# ultra-violet-tooth-sensor-mk-2_2.net
KiCad netlist of a schematic drawn in EAGLE
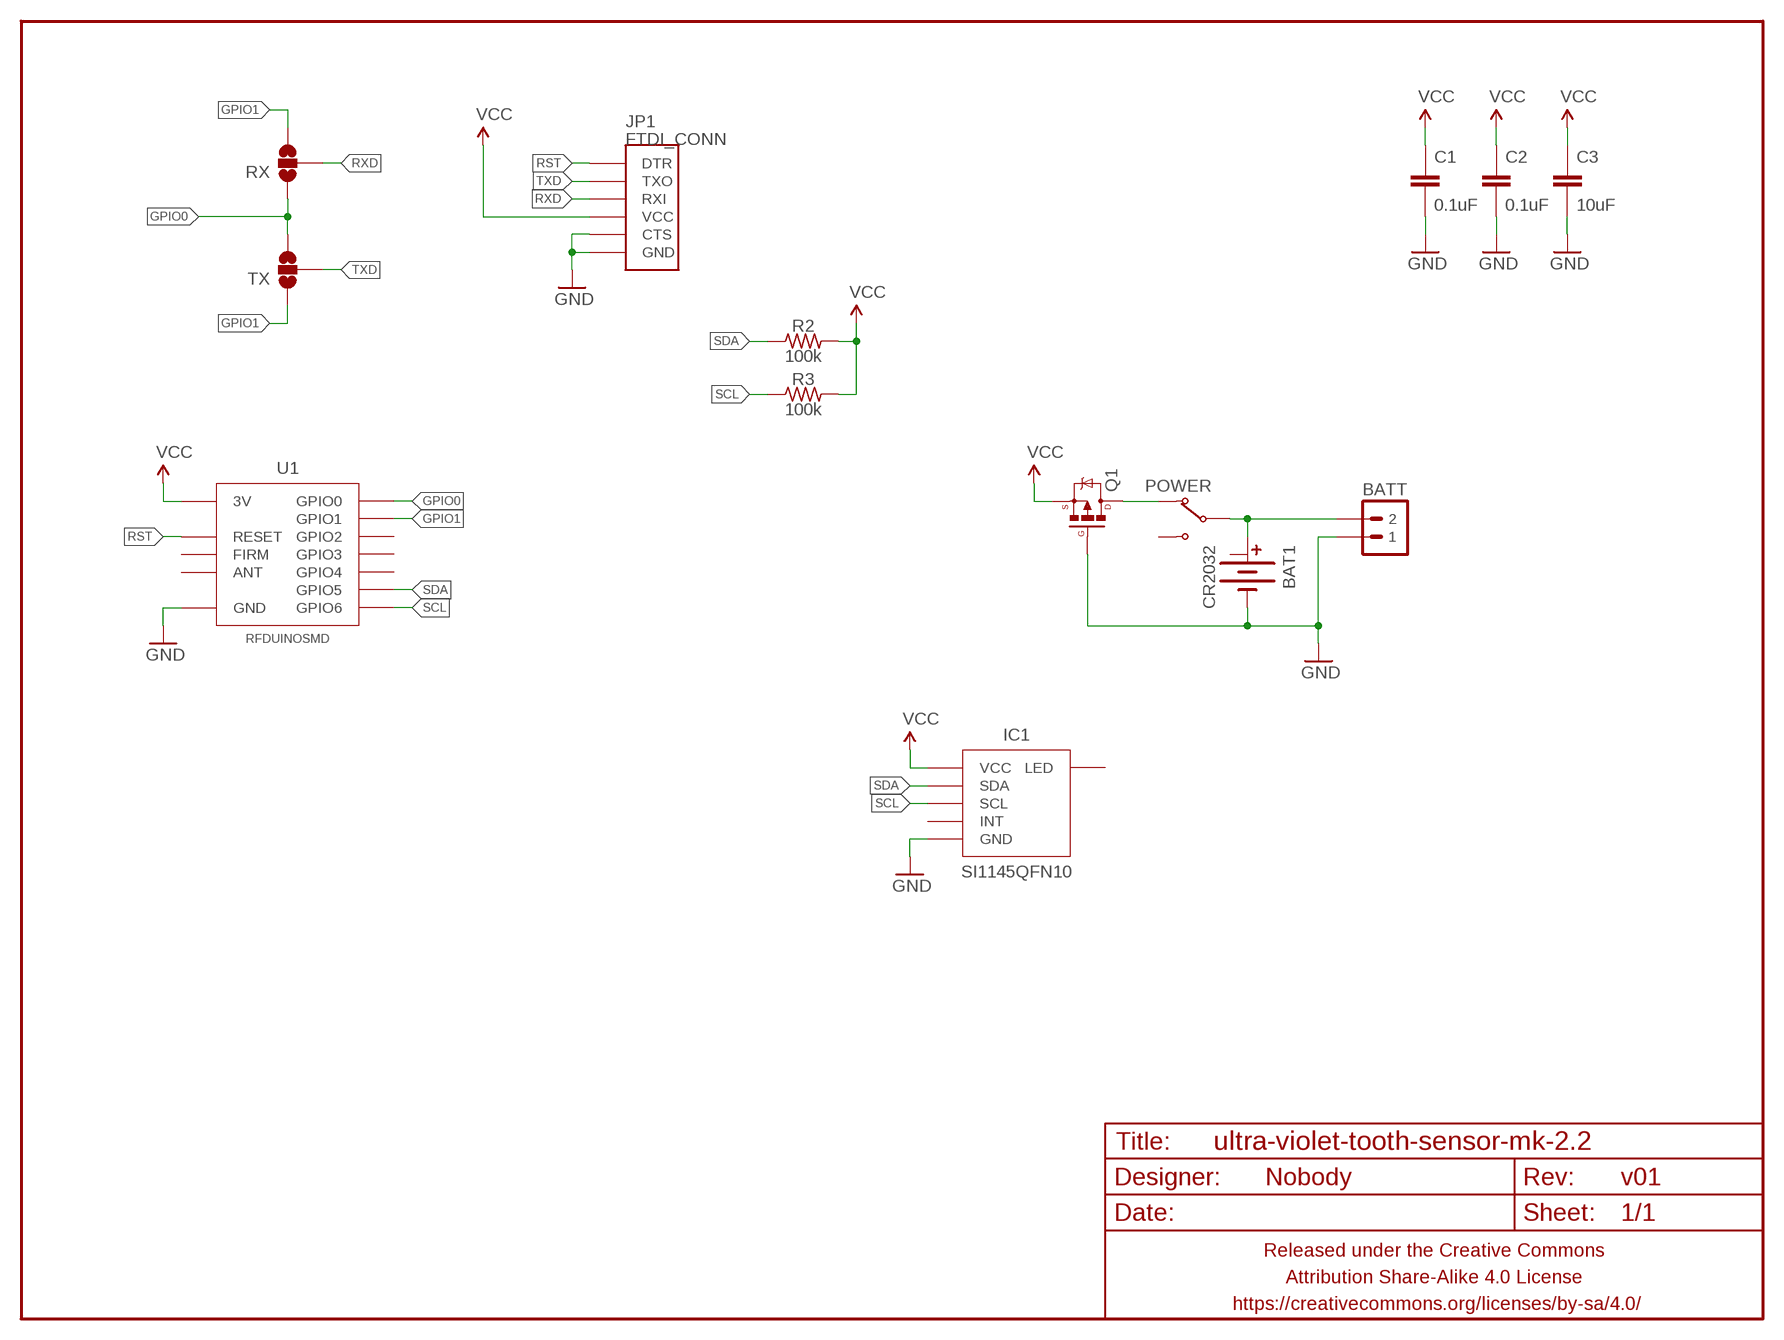
[diagram p0: schematic, sheet 1]

(export (version "E")
  (design (tool "Eeschema 10.0.6"))
  (components
    (comp (ref "BAT1")
      (value "CR2032")
      (footprint "eagle-import:BATTCON_20MM_MINE_STAHPIT")
      (libsource (lib "eagle-import") (part "BATTERY-COINCR2032_SMD_TIGHT"))
    )
    (comp (ref "BATT")
      (value "M02PTH-CENTERED-R+")
      (footprint "eagle-import:1X02-CENTER-R+")
      (libsource (lib "eagle-import") (part "M02PTH-CENTERED-R+"))
    )
    (comp (ref "C1")
      (value "0.1uF")
      (footprint "eagle-import:C0805")
      (libsource (lib "eagle-import") (part "CAPACITOR-CERAMICC0805"))
    )
    (comp (ref "C2")
      (value "0.1uF")
      (footprint "eagle-import:C0805")
      (libsource (lib "eagle-import") (part "CAPACITOR-CERAMICC0805"))
    )
    (comp (ref "C3")
      (value "10uF")
      (footprint "eagle-import:C1206")
      (libsource (lib "eagle-import") (part "CAPACITOR-CERAMICC1206"))
    )
    (comp (ref "FRAME1")
      (value "FRAME-LETTERNO_PACKAGE")
      (footprint "eagle-import:DUMMY")
      (fields (field (name "DESIGNER") "Nobody"))
      (libsource (lib "eagle-import") (part "FRAME-LETTERNO_PACKAGE"))
    )
    (comp (ref "IC1")
      (value "SI1145QFN10")
      (footprint "eagle-import:SI1145")
      (libsource (lib "eagle-import") (part "SI1145QFN10"))
    )
    (comp (ref "JP1")
      (value "FTDI_CONN")
      (footprint "eagle-import:FTDI_CONN")
      (libsource (lib "eagle-import") (part "FTDI_CONN"))
    )
    (comp (ref "POWER")
      (value "SWITCH-SPDTPTH-RA-2.54MM")
      (footprint "eagle-import:SPDT-RA-2.54MM")
      (libsource (lib "eagle-import") (part "SWITCH-SPDTPTH-RA-2.54MM"))
    )
    (comp (ref "Q1")
      (value "MOSFET-PCHANNELIRLML2244")
      (footprint "eagle-import:SOT23-3")
      (libsource (lib "eagle-import") (part "MOSFET-PCHANNELIRLML2244"))
    )
    (comp (ref "R2")
      (value "100k")
      (footprint "eagle-import:R0805")
      (libsource (lib "eagle-import") (part "RESISTORR0805"))
    )
    (comp (ref "R3")
      (value "100k")
      (footprint "eagle-import:R0805")
      (libsource (lib "eagle-import") (part "RESISTORR0805"))
    )
    (comp (ref "RX")
      (value "JUMPER-PAD-3-NOFULL_BOX_SILK")
      (footprint "eagle-import:PAD-JUMPER-3-NO_YES_SILK_FULL_BOX")
      (libsource (lib "eagle-import") (part "JUMPER-PAD-3-NOFULL_BOX_SILK"))
    )
    (comp (ref "TX")
      (value "JUMPER-PAD-3-NOFULL_BOX_SILK")
      (footprint "eagle-import:PAD-JUMPER-3-NO_YES_SILK_FULL_BOX")
      (libsource (lib "eagle-import") (part "JUMPER-PAD-3-NOFULL_BOX_SILK"))
    )
    (comp (ref "U1")
      (value "RFDUINOSMD")
      (footprint "eagle-import:RFDUINO-SMD")
      (libsource (lib "eagle-import") (part "RFDUINOSMD"))
    )
  )
  (nets
    (net (code "1") (name "GND") (class "Default")
      (node (ref "BAT1") (pin "BOTTOM") (pinfunction "-_BOTTOM") (pintype "bidirectional"))
      (node (ref "BATT") (pin "1") (pinfunction "1_1") (pintype "passive"))
      (node (ref "C1") (pin "2") (pinfunction "2_2") (pintype "passive"))
      (node (ref "C2") (pin "2") (pinfunction "2_2") (pintype "passive"))
      (node (ref "C3") (pin "2") (pinfunction "2_2") (pintype "passive"))
      (node (ref "IC1") (pin "GND") (pinfunction "GND_GND") (pintype "bidirectional"))
      (node (ref "JP1") (pin "CTS") (pinfunction "CTS_CTS") (pintype "bidirectional"))
      (node (ref "JP1") (pin "GND") (pinfunction "GND_GND") (pintype "bidirectional"))
      (node (ref "Q1") (pin "1") (pinfunction "G_1") (pintype "passive"))
      (node (ref "U1") (pin "GND@1") (pinfunction "GND_GND@1") (pintype "bidirectional"))
      (node (ref "U1") (pin "GND@2") (pinfunction "GND_GND@2") (pintype "bidirectional"))
      (node (ref "U1") (pin "GND@3") (pinfunction "GND_GND@3") (pintype "bidirectional"))
      (node (ref "U1") (pin "GND@4") (pinfunction "GND_GND@4") (pintype "bidirectional"))
      (node (ref "U1") (pin "GND@5") (pinfunction "GND_GND@5") (pintype "bidirectional"))
      (node (ref "U1") (pin "GND@6") (pinfunction "GND_GND@6") (pintype "bidirectional"))
      (node (ref "U1") (pin "GND@7") (pinfunction "GND_GND@7") (pintype "bidirectional"))
      (node (ref "U1") (pin "GND@8") (pinfunction "GND_GND@8") (pintype "bidirectional"))
    )
    (net (code "2") (name "GPIO0") (class "Default")
      (node (ref "RX") (pin "1") (pinfunction "1_1") (pintype "passive"))
      (node (ref "TX") (pin "3") (pinfunction "3_3") (pintype "passive"))
      (node (ref "U1") (pin "GPIO0") (pinfunction "GPIO0_GPIO0") (pintype "bidirectional"))
    )
    (net (code "3") (name "GPIO1") (class "Default")
      (node (ref "RX") (pin "3") (pinfunction "3_3") (pintype "passive"))
      (node (ref "TX") (pin "1") (pinfunction "1_1") (pintype "passive"))
      (node (ref "U1") (pin "GPIO1") (pinfunction "GPIO1_GPIO1") (pintype "bidirectional"))
    )
    (net (code "4") (name "Net-(BAT1-+)") (class "Default")
      (node (ref "BAT1") (pin "TOP@1") (pinfunction "+_TOP@1") (pintype "bidirectional"))
      (node (ref "BATT") (pin "2") (pinfunction "2_2") (pintype "passive"))
      (node (ref "POWER") (pin "2") (pinfunction "COM_2") (pintype "passive"))
    )
    (net (code "5") (name "Net-(POWER-NC)") (class "Default")
      (node (ref "POWER") (pin "1") (pinfunction "NC_1") (pintype "passive"))
      (node (ref "Q1") (pin "3") (pinfunction "D_3") (pintype "passive"))
    )
    (net (code "6") (name "RST") (class "Default")
      (node (ref "JP1") (pin "DTR") (pinfunction "DTR_DTR") (pintype "bidirectional"))
      (node (ref "U1") (pin "RESET") (pinfunction "RESET_RESET") (pintype "bidirectional"))
    )
    (net (code "7") (name "RXD") (class "Default")
      (node (ref "JP1") (pin "RXI") (pinfunction "RXI_RXI") (pintype "bidirectional"))
      (node (ref "RX") (pin "2") (pinfunction "2_2") (pintype "passive"))
    )
    (net (code "8") (name "SCL") (class "Default")
      (node (ref "IC1") (pin "SCL") (pinfunction "SCL_SCL") (pintype "bidirectional"))
      (node (ref "R3") (pin "1") (pinfunction "1_1") (pintype "passive"))
      (node (ref "U1") (pin "GPIO6") (pinfunction "GPIO6_GPIO6") (pintype "bidirectional"))
    )
    (net (code "9") (name "SDA") (class "Default")
      (node (ref "IC1") (pin "SDA") (pinfunction "SDA_SDA") (pintype "bidirectional"))
      (node (ref "R2") (pin "1") (pinfunction "1_1") (pintype "passive"))
      (node (ref "U1") (pin "GPIO5") (pinfunction "GPIO5_GPIO5") (pintype "bidirectional"))
    )
    (net (code "10") (name "TXD") (class "Default")
      (node (ref "JP1") (pin "TXO") (pinfunction "TXO_TXO") (pintype "bidirectional"))
      (node (ref "TX") (pin "2") (pinfunction "2_2") (pintype "passive"))
    )
    (net (code "11") (name "VCC") (class "Default")
      (node (ref "C1") (pin "1") (pinfunction "1_1") (pintype "passive"))
      (node (ref "C2") (pin "1") (pinfunction "1_1") (pintype "passive"))
      (node (ref "C3") (pin "1") (pinfunction "1_1") (pintype "passive"))
      (node (ref "IC1") (pin "VCC@1") (pinfunction "VCC_VCC@1") (pintype "bidirectional"))
      (node (ref "IC1") (pin "VCC@2") (pinfunction "VCC_VCC@2") (pintype "bidirectional"))
      (node (ref "IC1") (pin "VCC@3") (pinfunction "VCC_VCC@3") (pintype "bidirectional"))
      (node (ref "JP1") (pin "VCC") (pinfunction "VCC_VCC") (pintype "bidirectional"))
      (node (ref "Q1") (pin "2") (pinfunction "S_2") (pintype "passive"))
      (node (ref "R2") (pin "2") (pinfunction "2_2") (pintype "passive"))
      (node (ref "R3") (pin "2") (pinfunction "2_2") (pintype "passive"))
      (node (ref "U1") (pin "3V") (pinfunction "3V_3V") (pintype "bidirectional"))
    )
    (net (code "12") (name "unconnected-(BAT1-+1-PadTOP@2)") (class "Default")
      (node (ref "BAT1") (pin "TOP@2") (pinfunction "+1_TOP@2") (pintype "bidirectional"))
    )
    (net (code "13") (name "unconnected-(IC1-PadINT)") (class "Default")
      (node (ref "IC1") (pin "INT") (pinfunction "INT_INT") (pintype "bidirectional"))
    )
    (net (code "14") (name "unconnected-(IC1-PadLED)") (class "Default")
      (node (ref "IC1") (pin "LED") (pinfunction "LED_LED") (pintype "bidirectional"))
    )
    (net (code "15") (name "unconnected-(POWER-NO-Pad3)") (class "Default")
      (node (ref "POWER") (pin "3") (pinfunction "NO_3") (pintype "passive"))
    )
    (net (code "16") (name "unconnected-(U1-FIRM-PadFACTORY)") (class "Default")
      (node (ref "U1") (pin "FACTORY") (pinfunction "FIRM_FACTORY") (pintype "bidirectional"))
    )
    (net (code "17") (name "unconnected-(U1-PadANT)") (class "Default")
      (node (ref "U1") (pin "ANT") (pinfunction "ANT_ANT") (pintype "bidirectional"))
    )
    (net (code "18") (name "unconnected-(U1-PadGPIO2)") (class "Default")
      (node (ref "U1") (pin "GPIO2") (pinfunction "GPIO2_GPIO2") (pintype "bidirectional"))
    )
    (net (code "19") (name "unconnected-(U1-PadGPIO3)") (class "Default")
      (node (ref "U1") (pin "GPIO3") (pinfunction "GPIO3_GPIO3") (pintype "bidirectional"))
    )
    (net (code "20") (name "unconnected-(U1-PadGPIO4)") (class "Default")
      (node (ref "U1") (pin "GPIO4") (pinfunction "GPIO4_GPIO4") (pintype "bidirectional"))
    )
  )
)
